# Schematic.net
KiCad netlist of a schematic drawn in Altium Designer
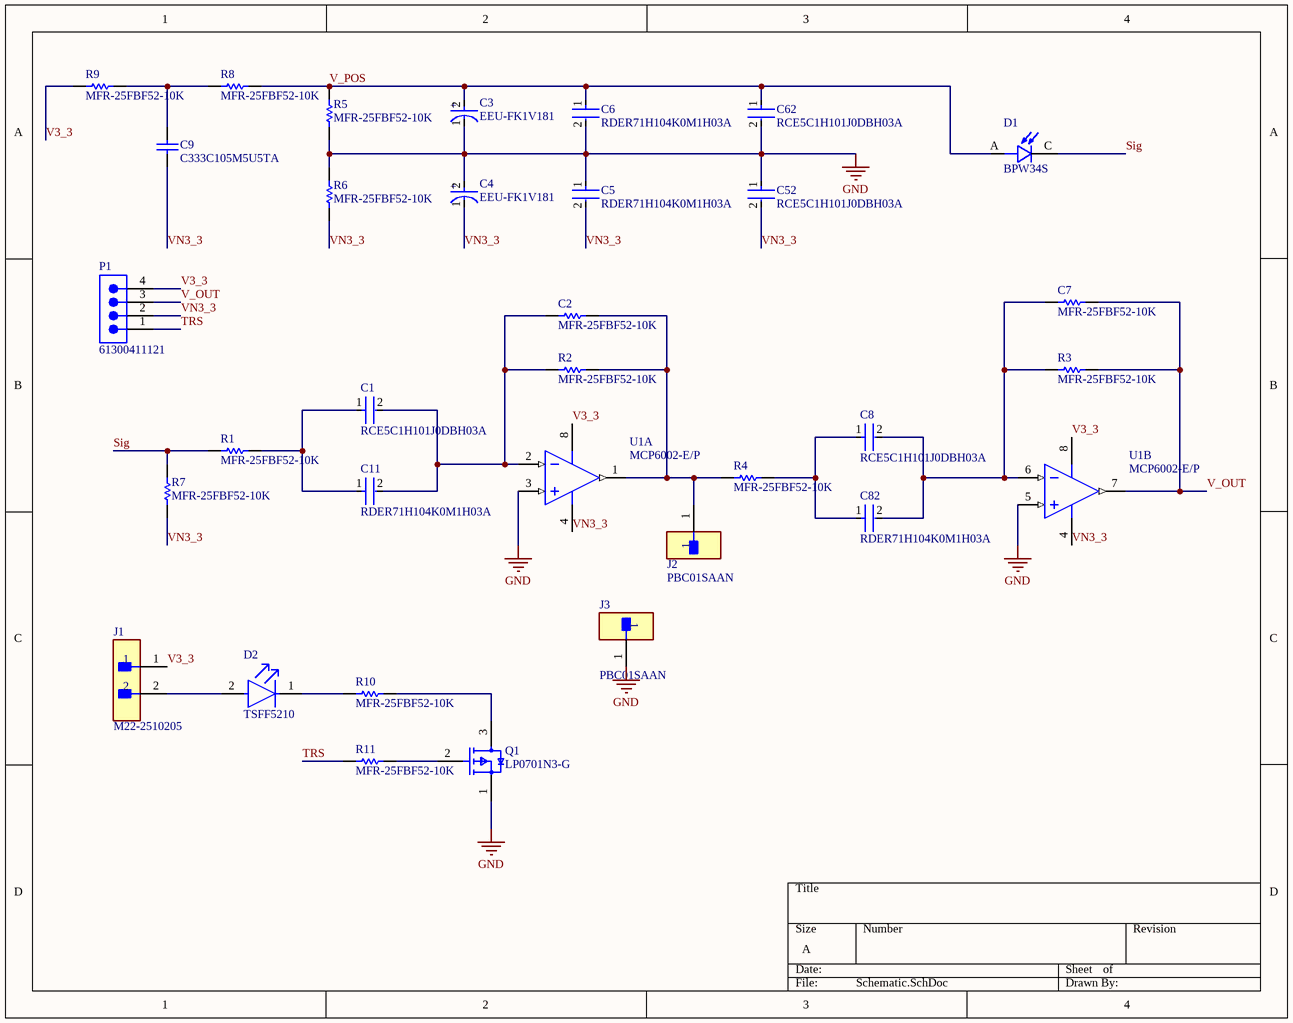
[diagram p0: Schematic.SchDoc]

(export (version "E")
  (design (tool "Eeschema 10.0.6"))
  (components
    (comp (ref "C1")
      (value "RCE5C1H101J0DBH03A")
      (footprint "FP-RCE0DB-MFG")
      (libsource (lib "Robert Harper") (part "b4654b650e69147ec39a6b967a45e02"))
    )
    (comp (ref "C2")
      (value "MFR-25FBF52-10K")
      (footprint "RESA60-630X240")
      (description "Fixed Resistor, Metal Film, 0.25W, 10000ohm, 250V, 1% +/-Tol, -100,100ppm/Cel")
      (fields (field (name "TOLERANCE") "1%") (field (name "POWER") "250mW"))
      (libsource (lib "Robert Harper") (part "RES-2"))
    )
    (comp (ref "C3")
      (value "EEU-FK1V181")
      (footprint "FP-RAD-TH-D_8_0_5-L_11_5-MFG")
      (libsource (lib "Robert Harper") (part "a00bbbee19879c290e62620ae7e47b1"))
    )
    (comp (ref "C4")
      (value "EEU-FK1V181")
      (footprint "FP-RAD-TH-D_8_0_5-L_11_5-MFG")
      (libsource (lib "Robert Harper") (part "a00bbbee19879c290e62620ae7e47b1"))
    )
    (comp (ref "C5")
      (value "RDER71H104K0M1H03A")
      (footprint "FP-RDE0M1-MFG")
      (libsource (lib "Robert Harper") (part "b4654b650e69147ec39a6b967a45e02"))
    )
    (comp (ref "C6")
      (value "RDER71H104K0M1H03A")
      (footprint "FP-RDE0M1-MFG")
      (libsource (lib "Robert Harper") (part "b4654b650e69147ec39a6b967a45e02"))
    )
    (comp (ref "C7")
      (value "MFR-25FBF52-10K")
      (footprint "RESA60-630X240")
      (description "Fixed Resistor, Metal Film, 0.25W, 10000ohm, 250V, 1% +/-Tol, -100,100ppm/Cel")
      (fields (field (name "TOLERANCE") "1%") (field (name "POWER") "250mW"))
      (libsource (lib "Robert Harper") (part "RES-2"))
    )
    (comp (ref "C8")
      (value "RCE5C1H101J0DBH03A")
      (footprint "FP-RCE0DB-MFG")
      (libsource (lib "Robert Harper") (part "b4654b650e69147ec39a6b967a45e02"))
    )
    (comp (ref "C9")
      (value "C333C105M5U5TA")
      (footprint "KEMT-C333C105M5U5TA-2")
      (libsource (lib "Robert Harper") (part "CAP-NP-2"))
    )
    (comp (ref "C11")
      (value "RDER71H104K0M1H03A")
      (footprint "FP-RDE0M1-MFG")
      (libsource (lib "Robert Harper") (part "b4654b650e69147ec39a6b967a45e02"))
    )
    (comp (ref "C52")
      (value "RCE5C1H101J0DBH03A")
      (footprint "FP-RCE0DB-MFG")
      (libsource (lib "Robert Harper") (part "b4654b650e69147ec39a6b967a45e02"))
    )
    (comp (ref "C62")
      (value "RCE5C1H101J0DBH03A")
      (footprint "FP-RCE0DB-MFG")
      (libsource (lib "Robert Harper") (part "b4654b650e69147ec39a6b967a45e02"))
    )
    (comp (ref "C82")
      (value "RDER71H104K0M1H03A")
      (footprint "FP-RDE0M1-MFG")
      (libsource (lib "Robert Harper") (part "b4654b650e69147ec39a6b967a45e02"))
    )
    (comp (ref "D1")
      (value "BPW34S")
      (footprint "DIO_BPW34S")
      (description "Photodiode 850nm 20ns 120Â° 2-SMD, Gull Wing")
      (fields (field (name "MF") "OSRAM Opto"))
      (libsource (lib "BPW34S") (part "BPW34S"))
    )
    (comp (ref "D2")
      (value "TSFF5210")
      (footprint "FP-6_544-5258_09-4-MFG")
      (description "Infrared LED, 5mm, 1-Element, 870nm")
      (libsource (lib "Robert Harper") (part "8706943c75ba83719d021d2fdc84c58"))
    )
    (comp (ref "J1")
      (value "M22-2510205")
      (footprint "FP-M22-2510205-MFG")
      (libsource (lib "Robert Harper") (part "3bc925449376181038e59eaffc5286c"))
    )
    (comp (ref "J2")
      (value "PBC01SAAN")
      (footprint "FP-PBC01SAAN-MFG")
      (description "Board Connector, 1 Contact(s), 1 Row(s), Male, Straight, 0.1 inch Pitch, Solder Terminal")
      (libsource (lib "") (part "dd45045ce8184df9e99e12baf3f412c_1"))
    )
    (comp (ref "J3")
      (value "PBC01SAAN")
      (footprint "FP-PBC01SAAN-MFG")
      (description "Board Connector, 1 Contact(s), 1 Row(s), Male, Straight, 0.1 inch Pitch, Solder Terminal")
      (libsource (lib "Robert Harper") (part "dd45045ce8184df9e99e12baf3f412c"))
    )
    (comp (ref "P1")
      (value "61300411121")
      (footprint "61300411121")
      (libsource (lib "Robert Harper") (part "Header_Male_1R_04P"))
    )
    (comp (ref "Q1")
      (value "LP0701N3-G")
      (footprint "FP-N3-MFG")
      (description "Mosfet; P-channel Enhancement-mode; -16.5V; 1.5 OHM3 TO-92BAG")
      (libsource (lib "Robert Harper") (part "d53c4972c00c3379e0fba722f59b06f"))
    )
    (comp (ref "R1")
      (value "MFR-25FBF52-10K")
      (footprint "RESA60-630X240")
      (description "Fixed Resistor, Metal Film, 0.25W, 10000ohm, 250V, 1% +/-Tol, -100,100ppm/Cel")
      (fields (field (name "TOLERANCE") "1%") (field (name "POWER") "250mW"))
      (libsource (lib "Robert Harper") (part "RES-2"))
    )
    (comp (ref "R2")
      (value "MFR-25FBF52-10K")
      (footprint "RESA60-630X240")
      (description "Fixed Resistor, Metal Film, 0.25W, 10000ohm, 250V, 1% +/-Tol, -100,100ppm/Cel")
      (fields (field (name "TOLERANCE") "1%") (field (name "POWER") "250mW"))
      (libsource (lib "Robert Harper") (part "RES-2"))
    )
    (comp (ref "R3")
      (value "MFR-25FBF52-10K")
      (footprint "RESA60-630X240")
      (description "Fixed Resistor, Metal Film, 0.25W, 10000ohm, 250V, 1% +/-Tol, -100,100ppm/Cel")
      (fields (field (name "TOLERANCE") "1%") (field (name "POWER") "250mW"))
      (libsource (lib "Robert Harper") (part "RES-2"))
    )
    (comp (ref "R4")
      (value "MFR-25FBF52-10K")
      (footprint "RESA60-630X240")
      (description "Fixed Resistor, Metal Film, 0.25W, 10000ohm, 250V, 1% +/-Tol, -100,100ppm/Cel")
      (fields (field (name "TOLERANCE") "1%") (field (name "POWER") "250mW"))
      (libsource (lib "Robert Harper") (part "RES-2"))
    )
    (comp (ref "R5")
      (value "MFR-25FBF52-10K")
      (footprint "RESA60-630X240")
      (description "Fixed Resistor, Metal Film, 0.25W, 10000ohm, 250V, 1% +/-Tol, -100,100ppm/Cel")
      (fields (field (name "TOLERANCE") "1%") (field (name "POWER") "250mW"))
      (libsource (lib "Robert Harper") (part "RES-2"))
    )
    (comp (ref "R6")
      (value "MFR-25FBF52-10K")
      (footprint "RESA60-630X240")
      (description "Fixed Resistor, Metal Film, 0.25W, 10000ohm, 250V, 1% +/-Tol, -100,100ppm/Cel")
      (fields (field (name "TOLERANCE") "1%") (field (name "POWER") "250mW"))
      (libsource (lib "Robert Harper") (part "RES-2"))
    )
    (comp (ref "R7")
      (value "MFR-25FBF52-10K")
      (footprint "RESA60-630X240")
      (description "Fixed Resistor, Metal Film, 0.25W, 10000ohm, 250V, 1% +/-Tol, -100,100ppm/Cel")
      (fields (field (name "TOLERANCE") "1%") (field (name "POWER") "250mW"))
      (libsource (lib "Robert Harper") (part "RES-2"))
    )
    (comp (ref "R8")
      (value "MFR-25FBF52-10K")
      (footprint "RESA60-630X240")
      (description "Fixed Resistor, Metal Film, 0.25W, 10000ohm, 250V, 1% +/-Tol, -100,100ppm/Cel")
      (fields (field (name "TOLERANCE") "1%") (field (name "POWER") "250mW"))
      (libsource (lib "Robert Harper") (part "RES-2"))
    )
    (comp (ref "R9")
      (value "MFR-25FBF52-10K")
      (footprint "RESA60-630X240")
      (description "Fixed Resistor, Metal Film, 0.25W, 10000ohm, 250V, 1% +/-Tol, -100,100ppm/Cel")
      (fields (field (name "TOLERANCE") "1%") (field (name "POWER") "250mW"))
      (libsource (lib "Robert Harper") (part "RES-2"))
    )
    (comp (ref "R10")
      (value "MFR-25FBF52-10K")
      (footprint "RESA60-630X240")
      (description "Fixed Resistor, Metal Film, 0.25W, 10000ohm, 250V, 1% +/-Tol, -100,100ppm/Cel")
      (fields (field (name "TOLERANCE") "1%") (field (name "POWER") "250mW"))
      (libsource (lib "Robert Harper") (part "RES-2"))
    )
    (comp (ref "R11")
      (value "MFR-25FBF52-10K")
      (footprint "RESA60-630X240")
      (description "Fixed Resistor, Metal Film, 0.25W, 10000ohm, 250V, 1% +/-Tol, -100,100ppm/Cel")
      (fields (field (name "TOLERANCE") "1%") (field (name "POWER") "250mW"))
      (libsource (lib "Robert Harper") (part "RES-2"))
    )
    (comp (ref "U1")
      (value "MCP6002-E/P")
      (footprint "PDIP300-P8")
      (description "Operational Amplifier, 2 Func, 4500uV Offset-Max, CMOS, PDIP8")
      (fields (field (name "POWER") "No"))
      (libsource (lib "Robert Harper") (part "AMP-OPA-MCP6002-IL8"))
    )
  )
  (nets
    (net (code "1") (name "/Sig") (class "Default")
      (node (ref "D1") (pin "C") (pinfunction "C_C") (pintype "passive"))
      (node (ref "R1") (pin "1") (pinfunction "1_1") (pintype "passive"))
      (node (ref "R7") (pin "2") (pinfunction "2_2") (pintype "passive"))
    )
    (net (code "2") (name "/TRS") (class "Default")
      (node (ref "P1") (pin "1") (pinfunction "1_1") (pintype "passive"))
      (node (ref "R11") (pin "1") (pinfunction "1_1") (pintype "passive"))
    )
    (net (code "3") (name "/V3_3") (class "Default")
      (node (ref "J1") (pin "1") (pinfunction "1_1") (pintype "passive"))
      (node (ref "P1") (pin "4") (pinfunction "4_4") (pintype "passive"))
      (node (ref "R9") (pin "1") (pinfunction "1_1") (pintype "passive"))
      (node (ref "U1") (pin "8") (pinfunction "VDD_8") (pintype "power_in"))
    )
    (net (code "4") (name "/VN3_3") (class "Default")
      (node (ref "C4") (pin "1") (pinfunction "C_1") (pintype "passive"))
      (node (ref "C5") (pin "2") (pinfunction "2_2") (pintype "passive"))
      (node (ref "C52") (pin "2") (pinfunction "2_2") (pintype "passive"))
      (node (ref "C9") (pin "1") (pinfunction "1_1") (pintype "passive"))
      (node (ref "P1") (pin "2") (pinfunction "2_2") (pintype "passive"))
      (node (ref "R6") (pin "1") (pinfunction "1_1") (pintype "passive"))
      (node (ref "R7") (pin "1") (pinfunction "1_1") (pintype "passive"))
      (node (ref "U1") (pin "4") (pinfunction "VSS_4") (pintype "power_in"))
    )
    (net (code "5") (name "/V_OUT") (class "Default")
      (node (ref "C7") (pin "2") (pinfunction "2_2") (pintype "passive"))
      (node (ref "P1") (pin "3") (pinfunction "3_3") (pintype "passive"))
      (node (ref "R3") (pin "2") (pinfunction "2_2") (pintype "passive"))
      (node (ref "U1") (pin "7") (pinfunction "VOUTB_7") (pintype "output"))
    )
    (net (code "6") (name "/V_POS") (class "Default")
      (node (ref "C3") (pin "2") (pinfunction "A_2") (pintype "passive"))
      (node (ref "C6") (pin "1") (pinfunction "1_1") (pintype "passive"))
      (node (ref "C62") (pin "1") (pinfunction "1_1") (pintype "passive"))
      (node (ref "D1") (pin "A") (pinfunction "A_A") (pintype "passive"))
      (node (ref "R5") (pin "2") (pinfunction "2_2") (pintype "passive"))
      (node (ref "R8") (pin "2") (pinfunction "2_2") (pintype "passive"))
    )
    (net (code "7") (name "GND") (class "Default")
      (node (ref "C3") (pin "1") (pinfunction "C_1") (pintype "passive"))
      (node (ref "C4") (pin "2") (pinfunction "A_2") (pintype "passive"))
      (node (ref "C5") (pin "1") (pinfunction "1_1") (pintype "passive"))
      (node (ref "C52") (pin "1") (pinfunction "1_1") (pintype "passive"))
      (node (ref "C6") (pin "2") (pinfunction "2_2") (pintype "passive"))
      (node (ref "C62") (pin "2") (pinfunction "2_2") (pintype "passive"))
      (node (ref "J3") (pin "1") (pinfunction "1_1") (pintype "passive"))
      (node (ref "Q1") (pin "1") (pinfunction "S_1") (pintype "passive"))
      (node (ref "R5") (pin "1") (pinfunction "1_1") (pintype "passive"))
      (node (ref "R6") (pin "2") (pinfunction "2_2") (pintype "passive"))
      (node (ref "U1") (pin "3") (pinfunction "VINA+_3") (pintype "input"))
      (node (ref "U1") (pin "5") (pinfunction "VINB+_5") (pintype "input"))
    )
    (net (code "8") (name "Net-(C1-Pad1)") (class "Default")
      (node (ref "C1") (pin "1") (pinfunction "1_1") (pintype "passive"))
      (node (ref "C11") (pin "1") (pinfunction "1_1") (pintype "passive"))
      (node (ref "R1") (pin "2") (pinfunction "2_2") (pintype "passive"))
    )
    (net (code "9") (name "Net-(C8-Pad1)") (class "Default")
      (node (ref "C8") (pin "1") (pinfunction "1_1") (pintype "passive"))
      (node (ref "C82") (pin "1") (pinfunction "1_1") (pintype "passive"))
      (node (ref "R4") (pin "2") (pinfunction "2_2") (pintype "passive"))
    )
    (net (code "10") (name "Net-(C9-Pad2)") (class "Default")
      (node (ref "C9") (pin "2") (pinfunction "2_2") (pintype "passive"))
      (node (ref "R8") (pin "1") (pinfunction "1_1") (pintype "passive"))
      (node (ref "R9") (pin "2") (pinfunction "2_2") (pintype "passive"))
    )
    (net (code "11") (name "Net-(D2-A)") (class "Default")
      (node (ref "D2") (pin "2") (pinfunction "A_2") (pintype "passive"))
      (node (ref "J1") (pin "2") (pinfunction "2_2") (pintype "passive"))
    )
    (net (code "12") (name "Net-(D2-C)") (class "Default")
      (node (ref "D2") (pin "1") (pinfunction "C_1") (pintype "passive"))
      (node (ref "R10") (pin "1") (pinfunction "1_1") (pintype "passive"))
    )
    (net (code "13") (name "Net-(Q1-D)") (class "Default")
      (node (ref "Q1") (pin "3") (pinfunction "D_3") (pintype "passive"))
      (node (ref "R10") (pin "2") (pinfunction "2_2") (pintype "passive"))
    )
    (net (code "14") (name "Net-(Q1-G)") (class "Default")
      (node (ref "Q1") (pin "2") (pinfunction "G_2") (pintype "passive"))
      (node (ref "R11") (pin "2") (pinfunction "2_2") (pintype "passive"))
    )
    (net (code "15") (name "Net-(U1A-VINA-)") (class "Default")
      (node (ref "C1") (pin "2") (pinfunction "2_2") (pintype "passive"))
      (node (ref "C11") (pin "2") (pinfunction "2_2") (pintype "passive"))
      (node (ref "C2") (pin "1") (pinfunction "1_1") (pintype "passive"))
      (node (ref "R2") (pin "1") (pinfunction "1_1") (pintype "passive"))
      (node (ref "U1") (pin "2") (pinfunction "VINA-_2") (pintype "input"))
    )
    (net (code "16") (name "Net-(U1A-VOUTA)") (class "Default")
      (node (ref "C2") (pin "2") (pinfunction "2_2") (pintype "passive"))
      (node (ref "J2") (pin "1") (pinfunction "1_1") (pintype "passive"))
      (node (ref "R2") (pin "2") (pinfunction "2_2") (pintype "passive"))
      (node (ref "R4") (pin "1") (pinfunction "1_1") (pintype "passive"))
      (node (ref "U1") (pin "1") (pinfunction "VOUTA_1") (pintype "output"))
    )
    (net (code "17") (name "Net-(U1B-VINB-)") (class "Default")
      (node (ref "C7") (pin "1") (pinfunction "1_1") (pintype "passive"))
      (node (ref "C8") (pin "2") (pinfunction "2_2") (pintype "passive"))
      (node (ref "C82") (pin "2") (pinfunction "2_2") (pintype "passive"))
      (node (ref "R3") (pin "1") (pinfunction "1_1") (pintype "passive"))
      (node (ref "U1") (pin "6") (pinfunction "VINB-_6") (pintype "input"))
    )
  )
)
